# Peripherals.net
KiCad netlist of a schematic drawn in Altium Designer
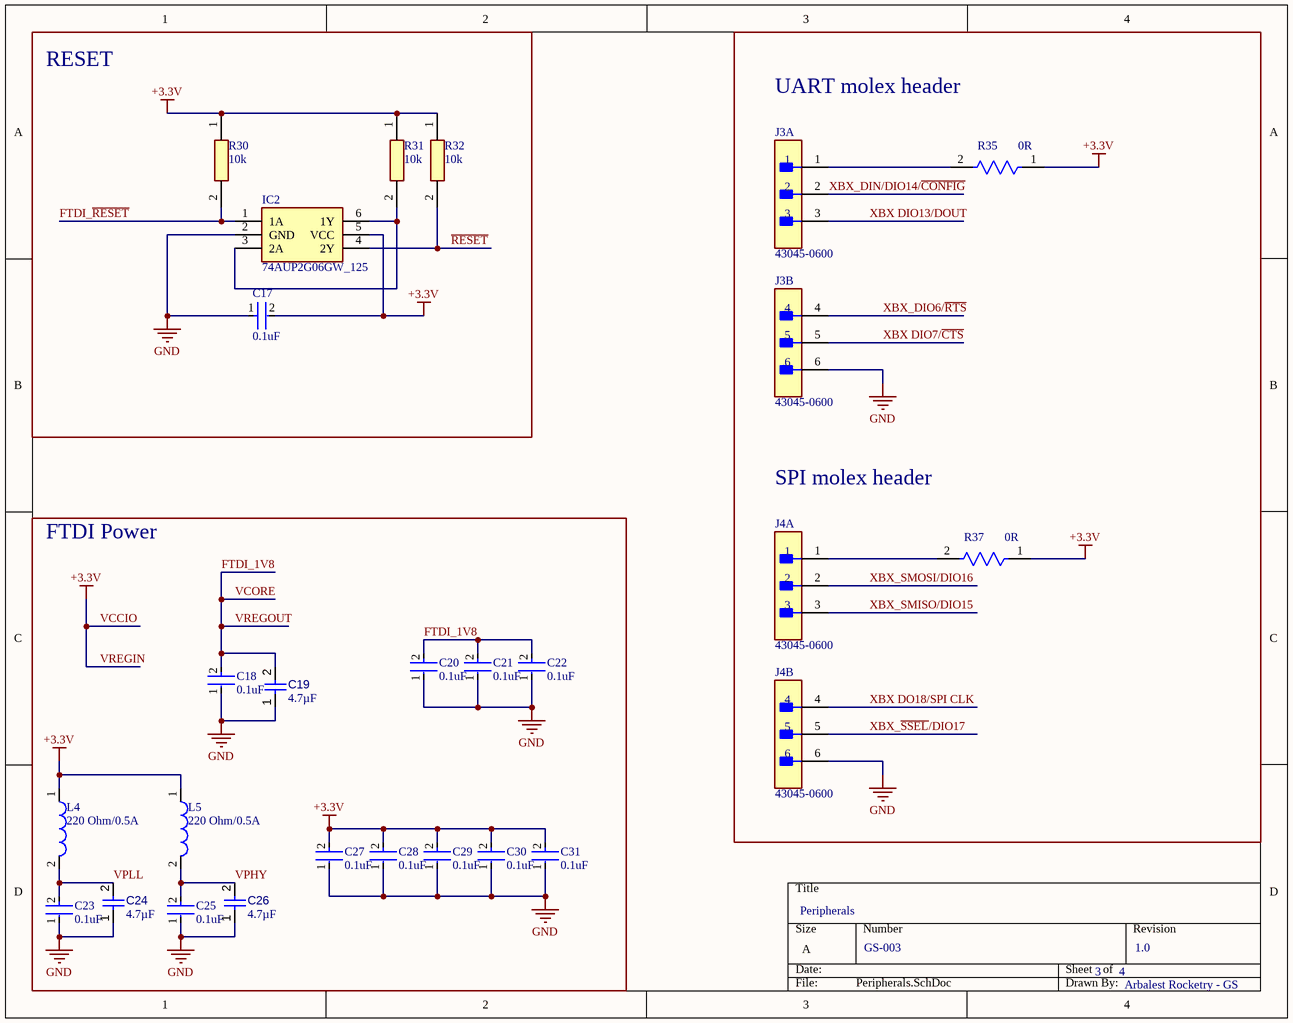
[diagram p0: Peripherals.SchDoc]

(export (version "E")
  (design (tool "Eeschema 10.0.6"))
  (components
    (comp (ref "C17")
      (value "0.1uF")
      (footprint "FP-CGA3E-0_3-0_1-IPC_A")
      (description "Cap Ceramic 100nF 50V X7R 20% Pad SMD 0603 +125°C Automotive T/R")
      (fields (field (name "TOLERANCE") "20%"))
      (libsource (lib "Altium Content Vault") (part "b4654b650e69147ec39a6b967a45e02"))
    )
    (comp (ref "C18")
      (value "0.1uF")
      (footprint "FP-GCJ188-0_2-IPC_C")
      (description "Cap Ceramic 0.1uF 50V X8R 10% Pad SMD 0603 Soft Termination +150°C Automotive T/R")
      (libsource (lib "Altium Content Vault") (part "f23184f103b6ebe33a8c269c53dcba6"))
    )
    (comp (ref "C19")
      (value "4.7µF")
      (footprint "CAPC0603(1608)100_L")
      (description "Chip Capacitor, 4.7µF +/-20%, 10V, 0603, Thickness 1 mm")
      (fields (field (name "TOLERANCE") "10%") (field (name "Comment") "Capacitor 4.7µF +/-20% 10V 0603"))
      (libsource (lib "York University") (part "CAP-NP-2"))
    )
    (comp (ref "C20")
      (value "0.1uF")
      (footprint "FP-GCJ188-0_2-IPC_C")
      (description "Cap Ceramic 0.1uF 50V X8R 10% Pad SMD 0603 Soft Termination +150°C Automotive T/R")
      (libsource (lib "Altium Content Vault") (part "f23184f103b6ebe33a8c269c53dcba6"))
    )
    (comp (ref "C21")
      (value "0.1uF")
      (footprint "FP-GCJ188-0_2-IPC_C")
      (description "Cap Ceramic 0.1uF 50V X8R 10% Pad SMD 0603 Soft Termination +150°C Automotive T/R")
      (libsource (lib "Altium Content Vault") (part "f23184f103b6ebe33a8c269c53dcba6"))
    )
    (comp (ref "C22")
      (value "0.1uF")
      (footprint "FP-GCJ188-0_2-IPC_C")
      (description "Cap Ceramic 0.1uF 50V X8R 10% Pad SMD 0603 Soft Termination +150°C Automotive T/R")
      (libsource (lib "Altium Content Vault") (part "f23184f103b6ebe33a8c269c53dcba6"))
    )
    (comp (ref "C23")
      (value "0.1uF")
      (footprint "FP-GCJ188-0_2-IPC_C")
      (description "Cap Ceramic 0.1uF 50V X8R 10% Pad SMD 0603 Soft Termination +150°C Automotive T/R")
      (libsource (lib "Altium Content Vault") (part "f23184f103b6ebe33a8c269c53dcba6"))
    )
    (comp (ref "C24")
      (value "4.7µF")
      (footprint "CAPC0603(1608)100_L")
      (description "Chip Capacitor, 4.7µF +/-20%, 10V, 0603, Thickness 1 mm")
      (fields (field (name "TOLERANCE") "10%") (field (name "Comment") "Capacitor 4.7µF +/-20% 10V 0603"))
      (libsource (lib "York University") (part "CAP-NP-2"))
    )
    (comp (ref "C25")
      (value "0.1uF")
      (footprint "FP-GCJ188-0_2-IPC_C")
      (description "Cap Ceramic 0.1uF 50V X8R 10% Pad SMD 0603 Soft Termination +150°C Automotive T/R")
      (libsource (lib "Altium Content Vault") (part "f23184f103b6ebe33a8c269c53dcba6"))
    )
    (comp (ref "C26")
      (value "4.7µF")
      (footprint "CAPC0603(1608)100_L")
      (description "Chip Capacitor, 4.7µF +/-20%, 10V, 0603, Thickness 1 mm")
      (fields (field (name "TOLERANCE") "10%") (field (name "Comment") "Capacitor 4.7µF +/-20% 10V 0603"))
      (libsource (lib "York University") (part "CAP-NP-2"))
    )
    (comp (ref "C27")
      (value "0.1uF")
      (footprint "FP-GCJ188-0_2-IPC_C")
      (description "Cap Ceramic 0.1uF 50V X8R 10% Pad SMD 0603 Soft Termination +150°C Automotive T/R")
      (libsource (lib "Altium Content Vault") (part "f23184f103b6ebe33a8c269c53dcba6"))
    )
    (comp (ref "C28")
      (value "0.1uF")
      (footprint "FP-GCJ188-0_2-IPC_C")
      (description "Cap Ceramic 0.1uF 50V X8R 10% Pad SMD 0603 Soft Termination +150°C Automotive T/R")
      (libsource (lib "Altium Content Vault") (part "f23184f103b6ebe33a8c269c53dcba6"))
    )
    (comp (ref "C29")
      (value "0.1uF")
      (footprint "FP-GCJ188-0_2-IPC_C")
      (description "Cap Ceramic 0.1uF 50V X8R 10% Pad SMD 0603 Soft Termination +150°C Automotive T/R")
      (libsource (lib "Altium Content Vault") (part "f23184f103b6ebe33a8c269c53dcba6"))
    )
    (comp (ref "C30")
      (value "0.1uF")
      (footprint "FP-GCJ188-0_2-IPC_C")
      (description "Cap Ceramic 0.1uF 50V X8R 10% Pad SMD 0603 Soft Termination +150°C Automotive T/R")
      (libsource (lib "Altium Content Vault") (part "f23184f103b6ebe33a8c269c53dcba6"))
    )
    (comp (ref "C31")
      (value "0.1uF")
      (footprint "FP-GCJ188-0_2-IPC_C")
      (description "Cap Ceramic 0.1uF 50V X8R 10% Pad SMD 0603 Soft Termination +150°C Automotive T/R")
      (libsource (lib "Altium Content Vault") (part "f23184f103b6ebe33a8c269c53dcba6"))
    )
    (comp (ref "IC2")
      (value "74AUP2G06GW_125")
      (footprint "SOT65P210X110-6N")
      (description "74AUP2G06 - Low-power dual inverter with open-drain output@en-us")
      (fields
        (field (name "MOUSER PART NUMBER") "771-74AUP2G06GW125")
        (field (name "MANUFACTURER_PART_NUMBER") "74AUP2G06GW,125")
      )
      (libsource (lib "York University") (part "74AUP2G06GW_125"))
    )
    (comp (ref "J3")
      (value "43045-0600")
      (footprint "FP-0430450600-MFG")
      (description "43045-0600 Connector Wire to Board Header 6 Position 3mm Solder Right Angle Thru-Hole Tray")
      (libsource (lib "Altium Content Vault") (part "7bb5f7ddfb2bec276e641070710345c"))
    )
    (comp (ref "J4")
      (value "43045-0600")
      (footprint "FP-0430450600-MFG")
      (description "43045-0600 Connector Wire to Board Header 6 Position 3mm Solder Right Angle Thru-Hole Tray")
      (libsource (lib "Altium Content Vault") (part "7bb5f7ddfb2bec276e641070710345c"))
    )
    (comp (ref "L4")
      (value "220 Ohm/0.5A")
      (footprint "SMD-0603")
      (description "SMD EMI Suppression Ferrite Bead WE-CBF, Z = 220 Ohm")
      (libsource (lib "Altium Content Vault") (part "PAS-IND-INDUCTOR-2"))
    )
    (comp (ref "L5")
      (value "220 Ohm/0.5A")
      (footprint "SMD-0603")
      (description "SMD EMI Suppression Ferrite Bead WE-CBF, Z = 220 Ohm")
      (libsource (lib "Altium Content Vault") (part "PAS-IND-INDUCTOR-2"))
    )
    (comp (ref "R30")
      (value "10k")
      (footprint "SamacSys:RESC1608X55N")
      (description "Resistor")
      (fields
        (field (name "MANUFACTURER_PART_NUMBER") "CR0603-FX-1002ELF")
        (field (name "MOUSER PART NUMBER") "652-CR0603FX-1002ELF")
      )
      (libsource (lib "*") (part "CR0603-FX-1002ELF"))
    )
    (comp (ref "R31")
      (value "10k")
      (footprint "SamacSys:RESC1608X55N")
      (description "Resistor")
      (fields
        (field (name "MANUFACTURER_PART_NUMBER") "CR0603-FX-1002ELF")
        (field (name "MOUSER PART NUMBER") "652-CR0603FX-1002ELF")
      )
      (libsource (lib "*") (part "CR0603-FX-1002ELF"))
    )
    (comp (ref "R32")
      (value "10k")
      (footprint "SamacSys:RESC1608X55N")
      (description "Resistor")
      (fields
        (field (name "MANUFACTURER_PART_NUMBER") "CR0603-FX-1002ELF")
        (field (name "MOUSER PART NUMBER") "652-CR0603FX-1002ELF")
      )
      (libsource (lib "*") (part "CR0603-FX-1002ELF"))
    )
    (comp (ref "R35")
      (value "0R")
      (footprint "FP-ERJ-3GEY0R00V-MFG")
      (description "RES SMD 0 OHM JUMPER 1/10W 0603")
      (fields (field (name "TOLERANCE") "5%") (field (name "MANUFACTURER PART NUMBER") "ERJ-3GEY0R00V"))
      (libsource (lib "Altium Content Vault") (part "1029c3af85768c4190bb7ad29bc67b5"))
    )
    (comp (ref "R37")
      (value "0R")
      (footprint "FP-ERJ-3GEY0R00V-MFG")
      (description "RES SMD 0 OHM JUMPER 1/10W 0603")
      (fields (field (name "TOLERANCE") "5%") (field (name "MANUFACTURER PART NUMBER") "ERJ-3GEY0R00V"))
      (libsource (lib "Altium Content Vault") (part "1029c3af85768c4190bb7ad29bc67b5"))
    )
  )
  (nets
    (net (code "1") (name "+3.3V") (class "Default")
      (node (ref "C17") (pin "2") (pinfunction "2_2") (pintype "passive"))
      (node (ref "C27") (pin "2") (pinfunction "2_2") (pintype "passive"))
      (node (ref "C28") (pin "2") (pinfunction "2_2") (pintype "passive"))
      (node (ref "C29") (pin "2") (pinfunction "2_2") (pintype "passive"))
      (node (ref "C30") (pin "2") (pinfunction "2_2") (pintype "passive"))
      (node (ref "C31") (pin "2") (pinfunction "2_2") (pintype "passive"))
      (node (ref "IC2") (pin "5") (pinfunction "VCC_5") (pintype "passive"))
      (node (ref "L4") (pin "1") (pinfunction "1_1") (pintype "passive"))
      (node (ref "L5") (pin "1") (pinfunction "1_1") (pintype "passive"))
      (node (ref "R30") (pin "1") (pinfunction "1_1") (pintype "passive"))
      (node (ref "R31") (pin "1") (pinfunction "1_1") (pintype "passive"))
      (node (ref "R32") (pin "1") (pinfunction "1_1") (pintype "passive"))
      (node (ref "R35") (pin "1") (pinfunction "1_1") (pintype "passive"))
      (node (ref "R37") (pin "1") (pinfunction "1_1") (pintype "passive"))
    )
    (net (code "2") (name "/FTDI_1V8") (class "Default")
      (node (ref "C18") (pin "2") (pinfunction "2_2") (pintype "passive"))
      (node (ref "C19") (pin "2") (pinfunction "2_2") (pintype "passive"))
      (node (ref "C20") (pin "2") (pinfunction "2_2") (pintype "passive"))
      (node (ref "C21") (pin "2") (pinfunction "2_2") (pintype "passive"))
      (node (ref "C22") (pin "2") (pinfunction "2_2") (pintype "passive"))
    )
    (net (code "3") (name "/FTDI_~{RESET}") (class "Default")
      (node (ref "IC2") (pin "1") (pinfunction "1A_1") (pintype "passive"))
      (node (ref "R30") (pin "2") (pinfunction "2_2") (pintype "passive"))
    )
    (net (code "4") (name "/VPHY") (class "Default")
      (node (ref "C25") (pin "2") (pinfunction "2_2") (pintype "passive"))
      (node (ref "C26") (pin "2") (pinfunction "2_2") (pintype "passive"))
      (node (ref "L5") (pin "2") (pinfunction "2_2") (pintype "passive"))
    )
    (net (code "5") (name "/VPLL") (class "Default")
      (node (ref "C23") (pin "2") (pinfunction "2_2") (pintype "passive"))
      (node (ref "C24") (pin "2") (pinfunction "2_2") (pintype "passive"))
      (node (ref "L4") (pin "2") (pinfunction "2_2") (pintype "passive"))
    )
    (net (code "6") (name "/XBX DIO7{slash}~{CTS}") (class "Default")
      (node (ref "J3") (pin "5") (pinfunction "5_5") (pintype "passive"))
    )
    (net (code "7") (name "/XBX DIO13{slash}DOUT") (class "Default")
      (node (ref "J3") (pin "3") (pinfunction "3_3") (pintype "passive"))
    )
    (net (code "8") (name "/XBX DO18{slash}SPI CLK") (class "Default")
      (node (ref "J4") (pin "4") (pinfunction "4_4") (pintype "passive"))
    )
    (net (code "9") (name "/XBX_DIN{slash}DIO14{slash}~{CONFIG}") (class "Default")
      (node (ref "J3") (pin "2") (pinfunction "2_2") (pintype "passive"))
    )
    (net (code "10") (name "/XBX_DIO6{slash}~{RTS}") (class "Default")
      (node (ref "J3") (pin "4") (pinfunction "4_4") (pintype "passive"))
    )
    (net (code "11") (name "/XBX_SMISO{slash}DIO15") (class "Default")
      (node (ref "J4") (pin "3") (pinfunction "3_3") (pintype "passive"))
    )
    (net (code "12") (name "/XBX_SMOSI{slash}DIO16") (class "Default")
      (node (ref "J4") (pin "2") (pinfunction "2_2") (pintype "passive"))
    )
    (net (code "13") (name "/XBX_~{SSEL}{slash}DIO17") (class "Default")
      (node (ref "J4") (pin "5") (pinfunction "5_5") (pintype "passive"))
    )
    (net (code "14") (name "/~{RESET}") (class "Default")
      (node (ref "IC2") (pin "4") (pinfunction "2Y_4") (pintype "passive"))
      (node (ref "R32") (pin "2") (pinfunction "2_2") (pintype "passive"))
    )
    (net (code "15") (name "GND") (class "Default")
      (node (ref "C17") (pin "1") (pinfunction "1_1") (pintype "passive"))
      (node (ref "C18") (pin "1") (pinfunction "1_1") (pintype "passive"))
      (node (ref "C19") (pin "1") (pinfunction "1_1") (pintype "passive"))
      (node (ref "C20") (pin "1") (pinfunction "1_1") (pintype "passive"))
      (node (ref "C21") (pin "1") (pinfunction "1_1") (pintype "passive"))
      (node (ref "C22") (pin "1") (pinfunction "1_1") (pintype "passive"))
      (node (ref "C23") (pin "1") (pinfunction "1_1") (pintype "passive"))
      (node (ref "C24") (pin "1") (pinfunction "1_1") (pintype "passive"))
      (node (ref "C25") (pin "1") (pinfunction "1_1") (pintype "passive"))
      (node (ref "C26") (pin "1") (pinfunction "1_1") (pintype "passive"))
      (node (ref "C27") (pin "1") (pinfunction "1_1") (pintype "passive"))
      (node (ref "C28") (pin "1") (pinfunction "1_1") (pintype "passive"))
      (node (ref "C29") (pin "1") (pinfunction "1_1") (pintype "passive"))
      (node (ref "C30") (pin "1") (pinfunction "1_1") (pintype "passive"))
      (node (ref "C31") (pin "1") (pinfunction "1_1") (pintype "passive"))
      (node (ref "IC2") (pin "2") (pinfunction "GND_2") (pintype "passive"))
      (node (ref "J3") (pin "6") (pinfunction "6_6") (pintype "passive"))
      (node (ref "J4") (pin "6") (pinfunction "6_6") (pintype "passive"))
    )
    (net (code "16") (name "Net-(IC2-1Y)") (class "Default")
      (node (ref "IC2") (pin "3") (pinfunction "2A_3") (pintype "passive"))
      (node (ref "IC2") (pin "6") (pinfunction "1Y_6") (pintype "passive"))
      (node (ref "R31") (pin "2") (pinfunction "2_2") (pintype "passive"))
    )
    (net (code "17") (name "Net-(J3-Pad1)") (class "Default")
      (node (ref "J3") (pin "1") (pinfunction "1_1") (pintype "passive"))
      (node (ref "R35") (pin "2") (pinfunction "2_2") (pintype "passive"))
    )
    (net (code "18") (name "Net-(J4-Pad1)") (class "Default")
      (node (ref "J4") (pin "1") (pinfunction "1_1") (pintype "passive"))
      (node (ref "R37") (pin "2") (pinfunction "2_2") (pintype "passive"))
    )
  )
)
